# Sensor_Interface.net
KiCad netlist of a schematic drawn in Altium Designer
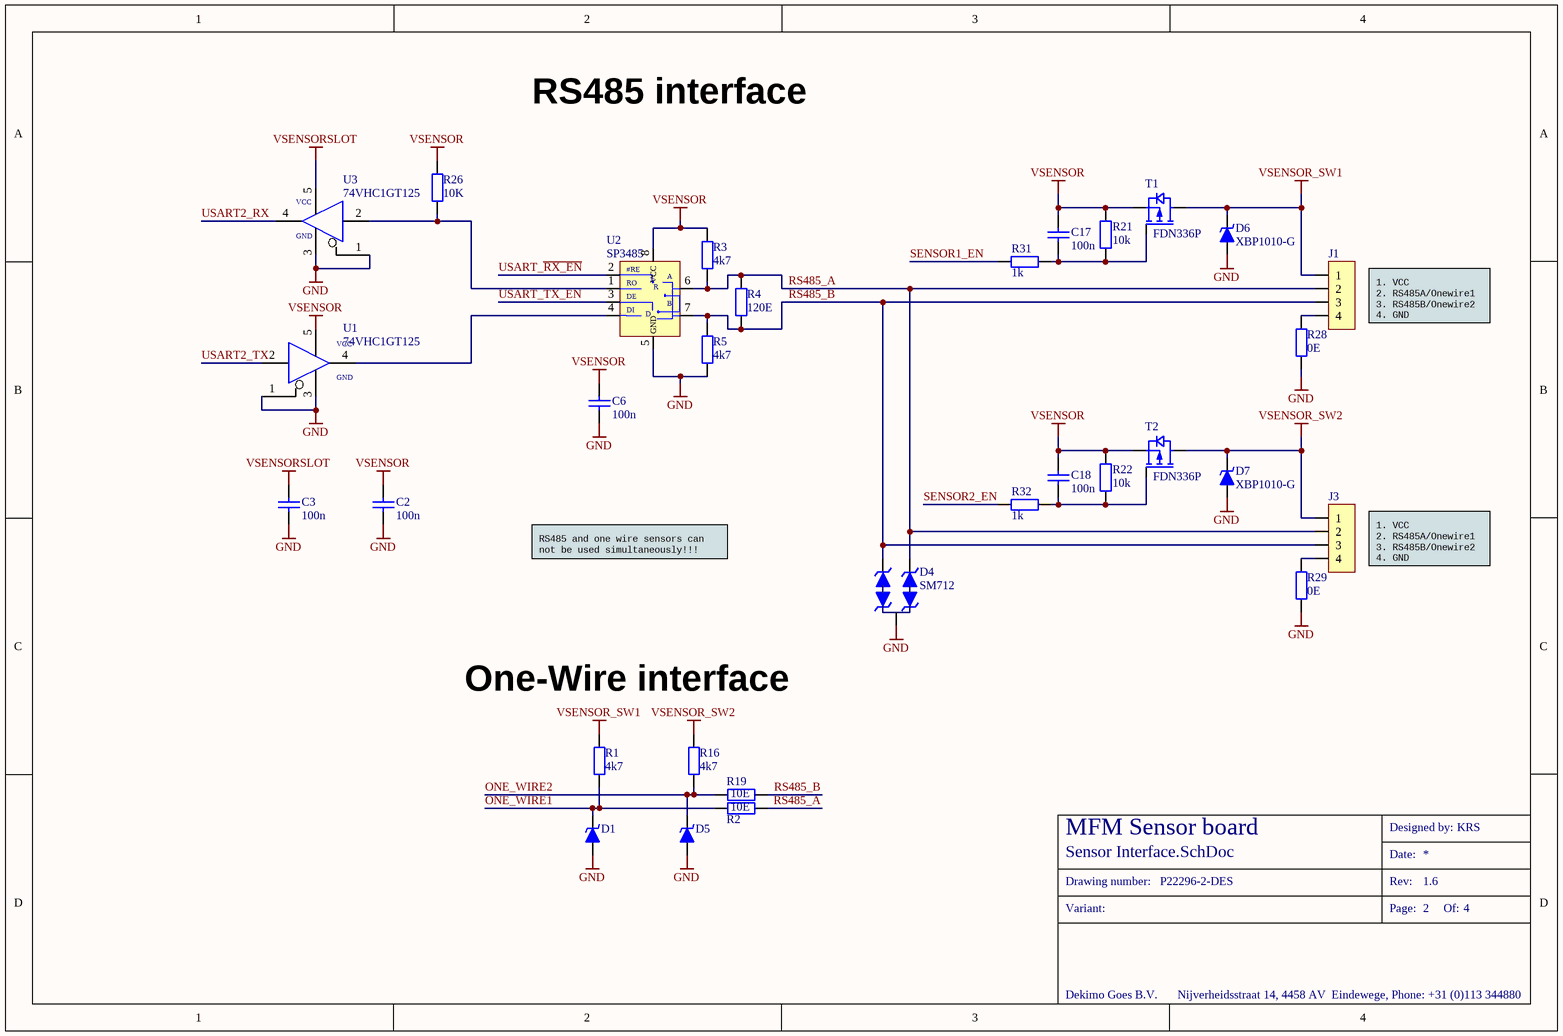
[diagram p0: Sensor Interface.SchDoc]

(export (version "E")
  (design (tool "Eeschema 10.0.6"))
  (components
    (comp (ref "C2")
      (value "100n")
      (footprint "CAPC1608X09N")
      (description "100nF 50V 10% X7R")
      (libsource (lib "DCI") (part "Capacitor_NP"))
    )
    (comp (ref "C3")
      (value "100n")
      (footprint "CAPC1608X09N")
      (description "100nF 50V 10% X7R")
      (libsource (lib "DCI") (part "Capacitor_NP"))
    )
    (comp (ref "C6")
      (value "100n")
      (footprint "CAPC1608X09N")
      (description "100nF 50V 10% X7R")
      (libsource (lib "DCI") (part "Capacitor_NP"))
    )
    (comp (ref "C17")
      (value "100n")
      (footprint "CAPC1608X09N")
      (description "100nF 50V 10% X7R")
      (libsource (lib "") (part "Capacitor_NP_1"))
    )
    (comp (ref "C18")
      (value "100n")
      (footprint "CAPC1608X09N")
      (description "100nF 50V 10% X7R")
      (libsource (lib "") (part "Capacitor_NP_1"))
    )
    (comp (ref "D1")
      (value "D3V3M1U2S9")
      (footprint "SOD946")
      (description "TVS diode 3.3V unidirec")
      (libsource (lib "DCI") (part "D_TVS"))
    )
    (comp (ref "D4")
      (value "SM712")
      (footprint "SOT95P245X110-C1C2C-3N")
      (description "7/12V, 400W bidir.")
      (libsource (lib "DCI") (part "D_TVS_Dual_Bi"))
    )
    (comp (ref "D5")
      (value "D3V3M1U2S9")
      (footprint "SOD946")
      (description "TVS diode 3.3V unidirec")
      (libsource (lib "DCI") (part "D_TVS"))
    )
    (comp (ref "D6")
      (value "XBP1010-G")
      (footprint "SODFL120X40-2N")
      (description "TVS Unidirectional 5V 40w")
      (libsource (lib "DCI") (part "D_TVS"))
    )
    (comp (ref "D7")
      (value "XBP1010-G")
      (footprint "SODFL120X40-2N")
      (description "TVS Unidirectional 5V 40w")
      (libsource (lib "DCI") (part "D_TVS"))
    )
    (comp (ref "J1")
      (value "4PIN")
      (footprint "WE_691322310004")
      (description "PCB,BOX,RY1,PEN4,HA,P3.81")
      (libsource (lib "DCI") (part "4PIN"))
    )
    (comp (ref "J3")
      (value "4PIN")
      (footprint "WE_691322310004")
      (description "PCB,BOX,RY1,PEN4,HA,P3.81")
      (libsource (lib "DCI") (part "4PIN"))
    )
    (comp (ref "R1")
      (value "4k7")
      (footprint "RESC1608X13N")
      (description "4k7 100mW 1% 0603")
      (libsource (lib "DCI") (part "Resistor"))
    )
    (comp (ref "R2")
      (value "10E")
      (footprint "RESC1608X13N")
      (description "10E 0.1W 1%")
      (libsource (lib "") (part "Resistor_2"))
    )
    (comp (ref "R3")
      (value "4k7")
      (footprint "RESC1608X13N")
      (description "4k7 100mW 1% 0603")
      (libsource (lib "DCI") (part "Resistor"))
    )
    (comp (ref "R4")
      (value "120E")
      (footprint "RESC1608X13N")
      (description "120E 0.1W 1%")
      (libsource (lib "DCI") (part "Resistor"))
    )
    (comp (ref "R5")
      (value "4k7")
      (footprint "RESC1608X13N")
      (description "4k7 100mW 1% 0603")
      (libsource (lib "DCI") (part "Resistor"))
    )
    (comp (ref "R16")
      (value "4k7")
      (footprint "RESC1608X13N")
      (description "4k7 100mW 1% 0603")
      (libsource (lib "DCI") (part "Resistor"))
    )
    (comp (ref "R19")
      (value "10E")
      (footprint "RESC1608X13N")
      (description "10E 0.1W 1%")
      (libsource (lib "") (part "Resistor_2"))
    )
    (comp (ref "R21")
      (value "10k")
      (footprint "RESC1608X13N")
      (description "10kΩ 100mW 1%")
      (libsource (lib "") (part "Resistor_1"))
    )
    (comp (ref "R22")
      (value "10k")
      (footprint "RESC1608X13N")
      (description "10kΩ 100mW 1%")
      (libsource (lib "") (part "Resistor_1"))
    )
    (comp (ref "R26")
      (value "10K")
      (footprint "RESC1608X13N")
      (description "10k 100mW, 1%")
      (libsource (lib "DCI") (part "Resistor"))
    )
    (comp (ref "R28")
      (value "0E")
      (footprint "RESC1608X13N")
      (description "0Ω 100mW 1%")
      (libsource (lib "") (part "Resistor_1"))
    )
    (comp (ref "R29")
      (value "0E")
      (footprint "RESC1608X13N")
      (description "0Ω 100mW 1%")
      (libsource (lib "") (part "Resistor_1"))
    )
    (comp (ref "R31")
      (value "1k")
      (footprint "RESC1005x04N")
      (description "1kΩ 62.5mW 1%")
      (libsource (lib "") (part "Resistor_3"))
    )
    (comp (ref "R32")
      (value "1k")
      (footprint "RESC1005x04N")
      (description "1kΩ 62.5mW 1%")
      (libsource (lib "") (part "Resistor_3"))
    )
    (comp (ref "T1")
      (value "FDN336P")
      (footprint "SOT95P245X110_GSD-3N")
      (description "20V 1.3A 200mΩ logic level")
      (libsource (lib "DCI") (part "P_Mosfet"))
    )
    (comp (ref "T2")
      (value "FDN336P")
      (footprint "SOT95P245X110_GSD-3N")
      (description "20V 1.3A 200mΩ logic level")
      (libsource (lib "DCI") (part "P_Mosfet"))
    )
    (comp (ref "U1")
      (value "74VHC1GT125")
      (footprint "SOT95P280X145-5N")
      (description "buffer/ levelshifter")
      (libsource (lib "DCI") (part "74VHC1G125"))
    )
    (comp (ref "U2")
      (value "SP3485")
      (footprint "SOIC127P600X175-8N")
      (description "RS485/RS422, 3v3, 10Mbps")
      (libsource (lib "DCI") (part "MAX483XSA"))
    )
    (comp (ref "U3")
      (value "74VHC1GT125")
      (footprint "SOT95P280X145-5N")
      (description "buffer/ levelshifter")
      (libsource (lib "DCI") (part "74VHC1G125"))
    )
  )
  (nets
    (net (code "1") (name "/ONE_WIRE1") (class "Default")
      (node (ref "D1") (pin "C") (pinfunction "C_C") (pintype "passive"))
      (node (ref "R1") (pin "1") (pinfunction "1_1") (pintype "passive"))
      (node (ref "R2") (pin "2") (pinfunction "2_2") (pintype "passive"))
    )
    (net (code "2") (name "/ONE_WIRE2") (class "Default")
      (node (ref "D5") (pin "C") (pinfunction "C_C") (pintype "passive"))
      (node (ref "R16") (pin "1") (pinfunction "1_1") (pintype "passive"))
      (node (ref "R19") (pin "2") (pinfunction "2_2") (pintype "passive"))
    )
    (net (code "3") (name "/RS485_A") (class "Default")
      (node (ref "D4") (pin "C2") (pintype "passive"))
      (node (ref "J1") (pin "2") (pinfunction "2_2") (pintype "passive"))
      (node (ref "J3") (pin "2") (pinfunction "2_2") (pintype "passive"))
      (node (ref "R2") (pin "1") (pinfunction "1_1") (pintype "passive"))
      (node (ref "R3") (pin "1") (pinfunction "1_1") (pintype "passive"))
      (node (ref "R4") (pin "2") (pinfunction "2_2") (pintype "passive"))
      (node (ref "U2") (pin "6") (pinfunction "A_6") (pintype "passive"))
    )
    (net (code "4") (name "/RS485_B") (class "Default")
      (node (ref "D4") (pin "C1") (pintype "passive"))
      (node (ref "J1") (pin "3") (pinfunction "3_3") (pintype "passive"))
      (node (ref "J3") (pin "3") (pinfunction "3_3") (pintype "passive"))
      (node (ref "R19") (pin "1") (pinfunction "1_1") (pintype "passive"))
      (node (ref "R4") (pin "1") (pinfunction "1_1") (pintype "passive"))
      (node (ref "R5") (pin "2") (pinfunction "2_2") (pintype "passive"))
      (node (ref "U2") (pin "7") (pinfunction "B_7") (pintype "passive"))
    )
    (net (code "5") (name "/SENSOR1_EN") (class "Default")
      (node (ref "R31") (pin "1") (pinfunction "1_1") (pintype "passive"))
    )
    (net (code "6") (name "/SENSOR2_EN") (class "Default")
      (node (ref "R32") (pin "1") (pinfunction "1_1") (pintype "passive"))
    )
    (net (code "7") (name "/USART2_RX") (class "Default")
      (node (ref "U3") (pin "4") (pinfunction "Y_4") (pintype "tri_state"))
    )
    (net (code "8") (name "/USART2_TX") (class "Default")
      (node (ref "U1") (pin "2") (pinfunction "A_2") (pintype "passive"))
    )
    (net (code "9") (name "/USART_TX_EN") (class "Default")
      (node (ref "U2") (pin "3") (pinfunction "DE_3") (pintype "passive"))
    )
    (net (code "10") (name "/USART_~{RX_EN}") (class "Default")
      (node (ref "U2") (pin "2") (pinfunction "~{RE}_2") (pintype "passive"))
    )
    (net (code "11") (name "GND") (class "Default")
      (node (ref "C2") (pin "1") (pinfunction "1_1") (pintype "passive"))
      (node (ref "C3") (pin "1") (pinfunction "1_1") (pintype "passive"))
      (node (ref "C6") (pin "1") (pinfunction "1_1") (pintype "passive"))
      (node (ref "D1") (pin "A") (pinfunction "A_A") (pintype "passive"))
      (node (ref "D4") (pin "C") (pintype "passive"))
      (node (ref "D5") (pin "A") (pinfunction "A_A") (pintype "passive"))
      (node (ref "D6") (pin "A") (pinfunction "A_A") (pintype "passive"))
      (node (ref "D7") (pin "A") (pinfunction "A_A") (pintype "passive"))
      (node (ref "R28") (pin "1") (pinfunction "1_1") (pintype "passive"))
      (node (ref "R29") (pin "1") (pinfunction "1_1") (pintype "passive"))
      (node (ref "R5") (pin "1") (pinfunction "1_1") (pintype "passive"))
      (node (ref "U1") (pin "1") (pinfunction "~{OE}_1") (pintype "passive"))
      (node (ref "U1") (pin "3") (pinfunction "GND_3") (pintype "power_in"))
      (node (ref "U2") (pin "5") (pinfunction "GND_5") (pintype "power_in"))
      (node (ref "U3") (pin "1") (pinfunction "~{OE}_1") (pintype "passive"))
      (node (ref "U3") (pin "3") (pinfunction "GND_3") (pintype "power_in"))
    )
    (net (code "12") (name "Net-(C17-Pad1)") (class "Default")
      (node (ref "C17") (pin "1") (pinfunction "1_1") (pintype "passive"))
      (node (ref "R21") (pin "1") (pinfunction "1_1") (pintype "passive"))
      (node (ref "R31") (pin "2") (pinfunction "2_2") (pintype "passive"))
      (node (ref "T1") (pin "G") (pinfunction "G_G") (pintype "passive"))
    )
    (net (code "13") (name "Net-(C18-Pad1)") (class "Default")
      (node (ref "C18") (pin "1") (pinfunction "1_1") (pintype "passive"))
      (node (ref "R22") (pin "1") (pinfunction "1_1") (pintype "passive"))
      (node (ref "R32") (pin "2") (pinfunction "2_2") (pintype "passive"))
      (node (ref "T2") (pin "G") (pinfunction "G_G") (pintype "passive"))
    )
    (net (code "14") (name "Net-(J1-Pad4)") (class "Default")
      (node (ref "J1") (pin "4") (pinfunction "4_4") (pintype "passive"))
      (node (ref "R28") (pin "2") (pinfunction "2_2") (pintype "passive"))
    )
    (net (code "15") (name "Net-(J3-Pad4)") (class "Default")
      (node (ref "J3") (pin "4") (pinfunction "4_4") (pintype "passive"))
      (node (ref "R29") (pin "2") (pinfunction "2_2") (pintype "passive"))
    )
    (net (code "16") (name "Net-(U1-Y)") (class "Default")
      (node (ref "U1") (pin "4") (pinfunction "Y_4") (pintype "tri_state"))
      (node (ref "U2") (pin "4") (pinfunction "DI_4") (pintype "passive"))
    )
    (net (code "17") (name "Net-(U2-RO)") (class "Default")
      (node (ref "R26") (pin "1") (pinfunction "1_1") (pintype "passive"))
      (node (ref "U2") (pin "1") (pinfunction "RO_1") (pintype "passive"))
      (node (ref "U3") (pin "2") (pinfunction "A_2") (pintype "passive"))
    )
    (net (code "18") (name "VSENSOR") (class "Default")
      (node (ref "C17") (pin "2") (pinfunction "2_2") (pintype "passive"))
      (node (ref "C18") (pin "2") (pinfunction "2_2") (pintype "passive"))
      (node (ref "C2") (pin "2") (pinfunction "2_2") (pintype "passive"))
      (node (ref "C6") (pin "2") (pinfunction "2_2") (pintype "passive"))
      (node (ref "R21") (pin "2") (pinfunction "2_2") (pintype "passive"))
      (node (ref "R22") (pin "2") (pinfunction "2_2") (pintype "passive"))
      (node (ref "R26") (pin "2") (pinfunction "2_2") (pintype "passive"))
      (node (ref "R3") (pin "2") (pinfunction "2_2") (pintype "passive"))
      (node (ref "T1") (pin "S") (pinfunction "S_S") (pintype "passive"))
      (node (ref "T2") (pin "S") (pinfunction "S_S") (pintype "passive"))
      (node (ref "U1") (pin "5") (pinfunction "VDD_5") (pintype "power_in"))
      (node (ref "U2") (pin "8") (pinfunction "VCC_8") (pintype "power_in"))
    )
    (net (code "19") (name "VSENSORSLOT") (class "Default")
      (node (ref "C3") (pin "2") (pinfunction "2_2") (pintype "passive"))
      (node (ref "U3") (pin "5") (pinfunction "VDD_5") (pintype "power_in"))
    )
    (net (code "20") (name "VSENSOR_SW1") (class "Default")
      (node (ref "D6") (pin "C") (pinfunction "C_C") (pintype "passive"))
      (node (ref "J1") (pin "1") (pinfunction "1_1") (pintype "passive"))
      (node (ref "R1") (pin "2") (pinfunction "2_2") (pintype "passive"))
      (node (ref "T1") (pin "D") (pinfunction "D_D") (pintype "passive"))
    )
    (net (code "21") (name "VSENSOR_SW2") (class "Default")
      (node (ref "D7") (pin "C") (pinfunction "C_C") (pintype "passive"))
      (node (ref "J3") (pin "1") (pinfunction "1_1") (pintype "passive"))
      (node (ref "R16") (pin "2") (pinfunction "2_2") (pintype "passive"))
      (node (ref "T2") (pin "D") (pinfunction "D_D") (pintype "passive"))
    )
  )
)
